# rs-485-multiplier-v2-x8.net
KiCad netlist of a schematic drawn in EAGLE
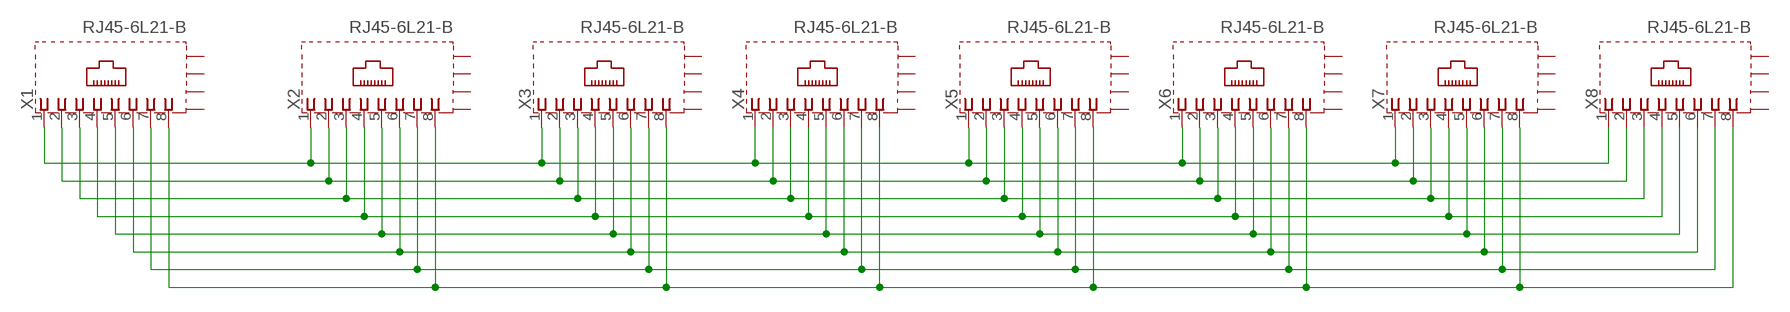
[diagram p0: schematic, sheet 1]

(export (version "E")
  (design (tool "Eeschema 10.0.6"))
  (components
    (comp (ref "X1")
      (value "RJ45-6L21-B")
      (footprint "eagle-import:RJ45-SHIELD1")
      (libsource (lib "eagle-import") (part "RJ4521-B-6L"))
    )
    (comp (ref "X2")
      (value "RJ45-6L21-B")
      (footprint "eagle-import:RJ45-SHIELD1")
      (libsource (lib "eagle-import") (part "RJ4521-B-6L"))
    )
    (comp (ref "X3")
      (value "RJ45-6L21-B")
      (footprint "eagle-import:RJ45-SHIELD1")
      (libsource (lib "eagle-import") (part "RJ4521-B-6L"))
    )
    (comp (ref "X4")
      (value "RJ45-6L21-B")
      (footprint "eagle-import:RJ45-SHIELD1")
      (libsource (lib "eagle-import") (part "RJ4521-B-6L"))
    )
    (comp (ref "X5")
      (value "RJ45-6L21-B")
      (footprint "eagle-import:RJ45-SHIELD1")
      (libsource (lib "eagle-import") (part "RJ4521-B-6L"))
    )
    (comp (ref "X6")
      (value "RJ45-6L21-B")
      (footprint "eagle-import:RJ45-SHIELD1")
      (libsource (lib "eagle-import") (part "RJ4521-B-6L"))
    )
    (comp (ref "X7")
      (value "RJ45-6L21-B")
      (footprint "eagle-import:RJ45-SHIELD1")
      (libsource (lib "eagle-import") (part "RJ4521-B-6L"))
    )
    (comp (ref "X8")
      (value "RJ45-6L21-B")
      (footprint "eagle-import:RJ45-SHIELD1")
      (libsource (lib "eagle-import") (part "RJ4521-B-6L"))
    )
  )
  (nets
    (net (code "1") (name "Net-(X1-Pad1)") (class "Default")
      (node (ref "X1") (pin "1") (pinfunction "1_1") (pintype "passive"))
      (node (ref "X2") (pin "1") (pinfunction "1_1") (pintype "passive"))
      (node (ref "X3") (pin "1") (pinfunction "1_1") (pintype "passive"))
      (node (ref "X4") (pin "1") (pinfunction "1_1") (pintype "passive"))
      (node (ref "X5") (pin "1") (pinfunction "1_1") (pintype "passive"))
      (node (ref "X6") (pin "1") (pinfunction "1_1") (pintype "passive"))
      (node (ref "X7") (pin "1") (pinfunction "1_1") (pintype "passive"))
      (node (ref "X8") (pin "1") (pinfunction "1_1") (pintype "passive"))
    )
    (net (code "2") (name "Net-(X1-Pad2)") (class "Default")
      (node (ref "X1") (pin "2") (pinfunction "2_2") (pintype "passive"))
      (node (ref "X2") (pin "2") (pinfunction "2_2") (pintype "passive"))
      (node (ref "X3") (pin "2") (pinfunction "2_2") (pintype "passive"))
      (node (ref "X4") (pin "2") (pinfunction "2_2") (pintype "passive"))
      (node (ref "X5") (pin "2") (pinfunction "2_2") (pintype "passive"))
      (node (ref "X6") (pin "2") (pinfunction "2_2") (pintype "passive"))
      (node (ref "X7") (pin "2") (pinfunction "2_2") (pintype "passive"))
      (node (ref "X8") (pin "2") (pinfunction "2_2") (pintype "passive"))
    )
    (net (code "3") (name "Net-(X1-Pad3)") (class "Default")
      (node (ref "X1") (pin "3") (pinfunction "3_3") (pintype "passive"))
      (node (ref "X2") (pin "3") (pinfunction "3_3") (pintype "passive"))
      (node (ref "X3") (pin "3") (pinfunction "3_3") (pintype "passive"))
      (node (ref "X4") (pin "3") (pinfunction "3_3") (pintype "passive"))
      (node (ref "X5") (pin "3") (pinfunction "3_3") (pintype "passive"))
      (node (ref "X6") (pin "3") (pinfunction "3_3") (pintype "passive"))
      (node (ref "X7") (pin "3") (pinfunction "3_3") (pintype "passive"))
      (node (ref "X8") (pin "3") (pinfunction "3_3") (pintype "passive"))
    )
    (net (code "4") (name "Net-(X1-Pad4)") (class "Default")
      (node (ref "X1") (pin "4") (pinfunction "4_4") (pintype "passive"))
      (node (ref "X2") (pin "4") (pinfunction "4_4") (pintype "passive"))
      (node (ref "X3") (pin "4") (pinfunction "4_4") (pintype "passive"))
      (node (ref "X4") (pin "4") (pinfunction "4_4") (pintype "passive"))
      (node (ref "X5") (pin "4") (pinfunction "4_4") (pintype "passive"))
      (node (ref "X6") (pin "4") (pinfunction "4_4") (pintype "passive"))
      (node (ref "X7") (pin "4") (pinfunction "4_4") (pintype "passive"))
      (node (ref "X8") (pin "4") (pinfunction "4_4") (pintype "passive"))
    )
    (net (code "5") (name "Net-(X1-Pad5)") (class "Default")
      (node (ref "X1") (pin "5") (pinfunction "5_5") (pintype "passive"))
      (node (ref "X2") (pin "5") (pinfunction "5_5") (pintype "passive"))
      (node (ref "X3") (pin "5") (pinfunction "5_5") (pintype "passive"))
      (node (ref "X4") (pin "5") (pinfunction "5_5") (pintype "passive"))
      (node (ref "X5") (pin "5") (pinfunction "5_5") (pintype "passive"))
      (node (ref "X6") (pin "5") (pinfunction "5_5") (pintype "passive"))
      (node (ref "X7") (pin "5") (pinfunction "5_5") (pintype "passive"))
      (node (ref "X8") (pin "5") (pinfunction "5_5") (pintype "passive"))
    )
    (net (code "6") (name "Net-(X1-Pad6)") (class "Default")
      (node (ref "X1") (pin "6") (pinfunction "6_6") (pintype "passive"))
      (node (ref "X2") (pin "6") (pinfunction "6_6") (pintype "passive"))
      (node (ref "X3") (pin "6") (pinfunction "6_6") (pintype "passive"))
      (node (ref "X4") (pin "6") (pinfunction "6_6") (pintype "passive"))
      (node (ref "X5") (pin "6") (pinfunction "6_6") (pintype "passive"))
      (node (ref "X6") (pin "6") (pinfunction "6_6") (pintype "passive"))
      (node (ref "X7") (pin "6") (pinfunction "6_6") (pintype "passive"))
      (node (ref "X8") (pin "6") (pinfunction "6_6") (pintype "passive"))
    )
    (net (code "7") (name "Net-(X1-Pad7)") (class "Default")
      (node (ref "X1") (pin "7") (pinfunction "7_7") (pintype "passive"))
      (node (ref "X2") (pin "7") (pinfunction "7_7") (pintype "passive"))
      (node (ref "X3") (pin "7") (pinfunction "7_7") (pintype "passive"))
      (node (ref "X4") (pin "7") (pinfunction "7_7") (pintype "passive"))
      (node (ref "X5") (pin "7") (pinfunction "7_7") (pintype "passive"))
      (node (ref "X6") (pin "7") (pinfunction "7_7") (pintype "passive"))
      (node (ref "X7") (pin "7") (pinfunction "7_7") (pintype "passive"))
      (node (ref "X8") (pin "7") (pinfunction "7_7") (pintype "passive"))
    )
    (net (code "8") (name "Net-(X1-Pad8)") (class "Default")
      (node (ref "X1") (pin "8") (pinfunction "8_8") (pintype "passive"))
      (node (ref "X2") (pin "8") (pinfunction "8_8") (pintype "passive"))
      (node (ref "X3") (pin "8") (pinfunction "8_8") (pintype "passive"))
      (node (ref "X4") (pin "8") (pinfunction "8_8") (pintype "passive"))
      (node (ref "X5") (pin "8") (pinfunction "8_8") (pintype "passive"))
      (node (ref "X6") (pin "8") (pinfunction "8_8") (pintype "passive"))
      (node (ref "X7") (pin "8") (pinfunction "8_8") (pintype "passive"))
      (node (ref "X8") (pin "8") (pinfunction "8_8") (pintype "passive"))
    )
    (net (code "9") (name "unconnected-(X1-S-PadS1)") (class "Default")
      (node (ref "X1") (pin "S1") (pinfunction "S_S1") (pintype "passive"))
    )
    (net (code "10") (name "unconnected-(X1-S-PadS2)") (class "Default")
      (node (ref "X1") (pin "S2") (pinfunction "S_S2") (pintype "passive"))
    )
    (net (code "11") (name "unconnected-(X1-S-PadS3)") (class "Default")
      (node (ref "X1") (pin "S3") (pinfunction "S_S3") (pintype "passive"))
    )
    (net (code "12") (name "unconnected-(X1-S-PadS4)") (class "Default")
      (node (ref "X1") (pin "S4") (pinfunction "S_S4") (pintype "passive"))
    )
    (net (code "13") (name "unconnected-(X2-S-PadS1)") (class "Default")
      (node (ref "X2") (pin "S1") (pinfunction "S_S1") (pintype "passive"))
    )
    (net (code "14") (name "unconnected-(X2-S-PadS2)") (class "Default")
      (node (ref "X2") (pin "S2") (pinfunction "S_S2") (pintype "passive"))
    )
    (net (code "15") (name "unconnected-(X2-S-PadS3)") (class "Default")
      (node (ref "X2") (pin "S3") (pinfunction "S_S3") (pintype "passive"))
    )
    (net (code "16") (name "unconnected-(X2-S-PadS4)") (class "Default")
      (node (ref "X2") (pin "S4") (pinfunction "S_S4") (pintype "passive"))
    )
    (net (code "17") (name "unconnected-(X3-S-PadS1)") (class "Default")
      (node (ref "X3") (pin "S1") (pinfunction "S_S1") (pintype "passive"))
    )
    (net (code "18") (name "unconnected-(X3-S-PadS2)") (class "Default")
      (node (ref "X3") (pin "S2") (pinfunction "S_S2") (pintype "passive"))
    )
    (net (code "19") (name "unconnected-(X3-S-PadS3)") (class "Default")
      (node (ref "X3") (pin "S3") (pinfunction "S_S3") (pintype "passive"))
    )
    (net (code "20") (name "unconnected-(X3-S-PadS4)") (class "Default")
      (node (ref "X3") (pin "S4") (pinfunction "S_S4") (pintype "passive"))
    )
    (net (code "21") (name "unconnected-(X4-S-PadS1)") (class "Default")
      (node (ref "X4") (pin "S1") (pinfunction "S_S1") (pintype "passive"))
    )
    (net (code "22") (name "unconnected-(X4-S-PadS2)") (class "Default")
      (node (ref "X4") (pin "S2") (pinfunction "S_S2") (pintype "passive"))
    )
    (net (code "23") (name "unconnected-(X4-S-PadS3)") (class "Default")
      (node (ref "X4") (pin "S3") (pinfunction "S_S3") (pintype "passive"))
    )
    (net (code "24") (name "unconnected-(X4-S-PadS4)") (class "Default")
      (node (ref "X4") (pin "S4") (pinfunction "S_S4") (pintype "passive"))
    )
    (net (code "25") (name "unconnected-(X5-S-PadS1)") (class "Default")
      (node (ref "X5") (pin "S1") (pinfunction "S_S1") (pintype "passive"))
    )
    (net (code "26") (name "unconnected-(X5-S-PadS2)") (class "Default")
      (node (ref "X5") (pin "S2") (pinfunction "S_S2") (pintype "passive"))
    )
    (net (code "27") (name "unconnected-(X5-S-PadS3)") (class "Default")
      (node (ref "X5") (pin "S3") (pinfunction "S_S3") (pintype "passive"))
    )
    (net (code "28") (name "unconnected-(X5-S-PadS4)") (class "Default")
      (node (ref "X5") (pin "S4") (pinfunction "S_S4") (pintype "passive"))
    )
    (net (code "29") (name "unconnected-(X6-S-PadS1)") (class "Default")
      (node (ref "X6") (pin "S1") (pinfunction "S_S1") (pintype "passive"))
    )
    (net (code "30") (name "unconnected-(X6-S-PadS2)") (class "Default")
      (node (ref "X6") (pin "S2") (pinfunction "S_S2") (pintype "passive"))
    )
    (net (code "31") (name "unconnected-(X6-S-PadS3)") (class "Default")
      (node (ref "X6") (pin "S3") (pinfunction "S_S3") (pintype "passive"))
    )
    (net (code "32") (name "unconnected-(X6-S-PadS4)") (class "Default")
      (node (ref "X6") (pin "S4") (pinfunction "S_S4") (pintype "passive"))
    )
    (net (code "33") (name "unconnected-(X7-S-PadS1)") (class "Default")
      (node (ref "X7") (pin "S1") (pinfunction "S_S1") (pintype "passive"))
    )
    (net (code "34") (name "unconnected-(X7-S-PadS2)") (class "Default")
      (node (ref "X7") (pin "S2") (pinfunction "S_S2") (pintype "passive"))
    )
    (net (code "35") (name "unconnected-(X7-S-PadS3)") (class "Default")
      (node (ref "X7") (pin "S3") (pinfunction "S_S3") (pintype "passive"))
    )
    (net (code "36") (name "unconnected-(X7-S-PadS4)") (class "Default")
      (node (ref "X7") (pin "S4") (pinfunction "S_S4") (pintype "passive"))
    )
    (net (code "37") (name "unconnected-(X8-S-PadS1)") (class "Default")
      (node (ref "X8") (pin "S1") (pinfunction "S_S1") (pintype "passive"))
    )
    (net (code "38") (name "unconnected-(X8-S-PadS2)") (class "Default")
      (node (ref "X8") (pin "S2") (pinfunction "S_S2") (pintype "passive"))
    )
    (net (code "39") (name "unconnected-(X8-S-PadS3)") (class "Default")
      (node (ref "X8") (pin "S3") (pinfunction "S_S3") (pintype "passive"))
    )
    (net (code "40") (name "unconnected-(X8-S-PadS4)") (class "Default")
      (node (ref "X8") (pin "S4") (pinfunction "S_S4") (pintype "passive"))
    )
  )
)
